# SCH_Shell_MotorsportV2.net
KiCad netlist of a schematic drawn in EasyEDA
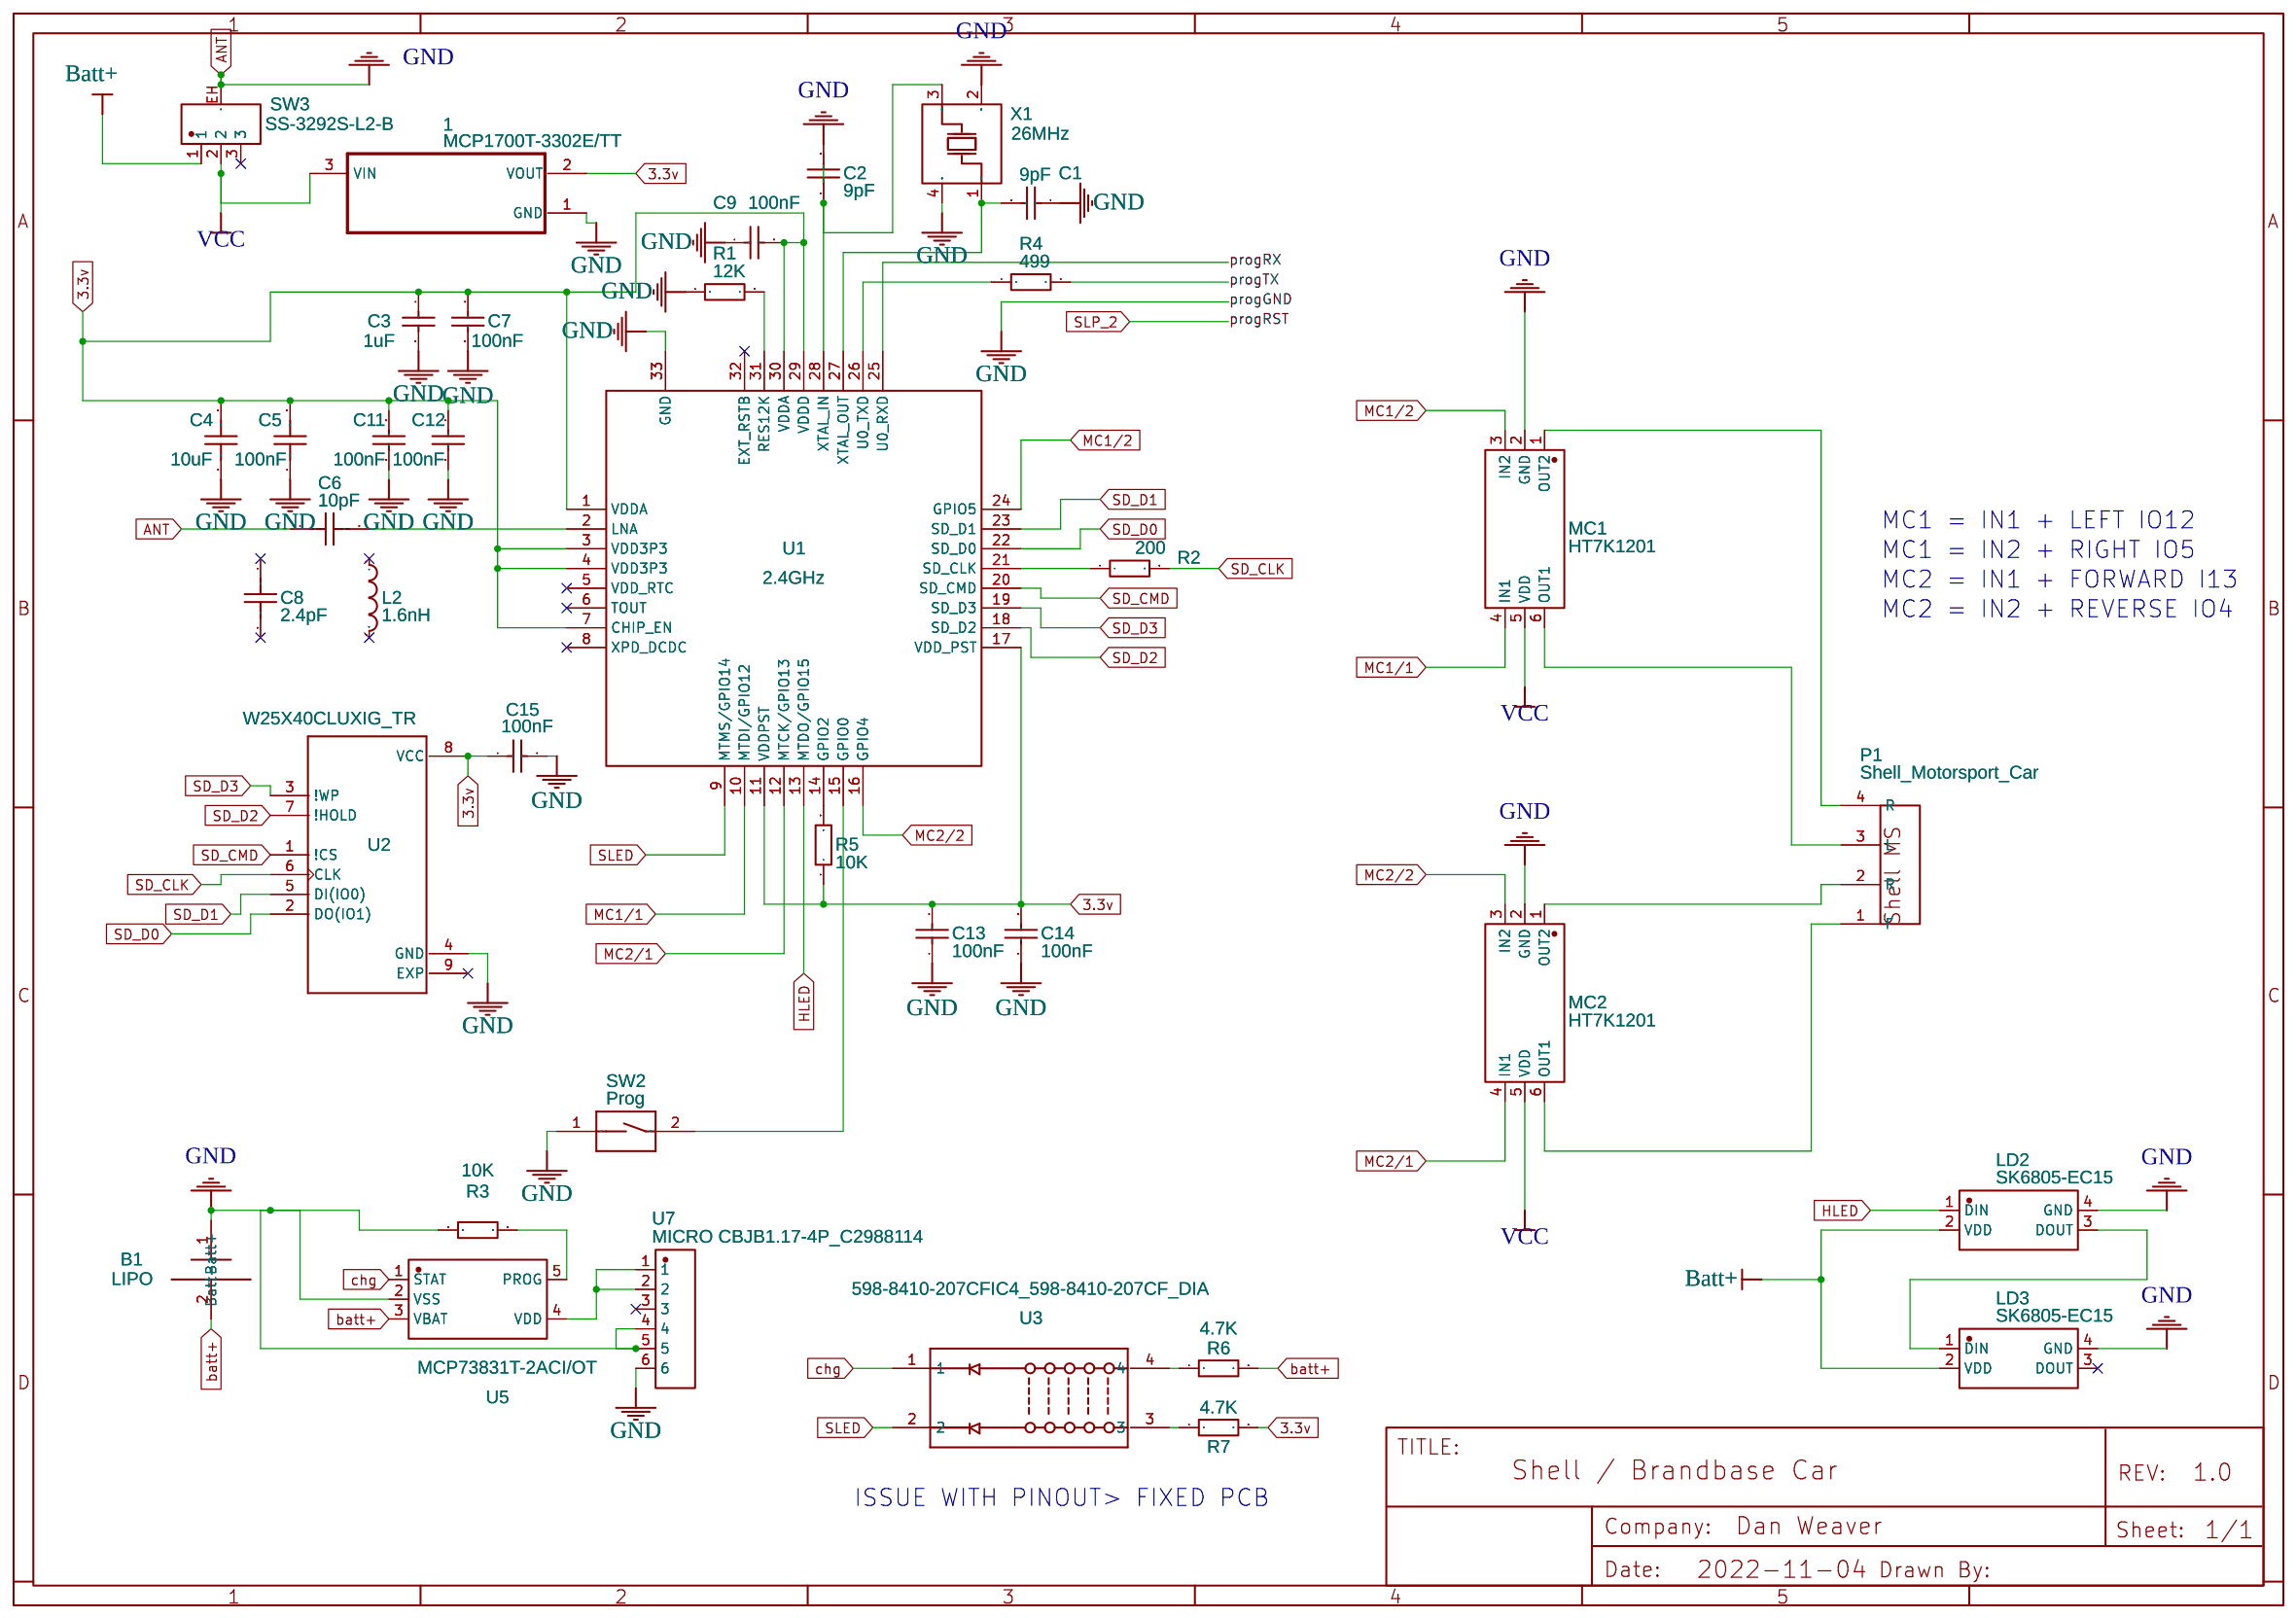
[diagram p0: schematic sheet]

(export (version "E")
  (design (tool "Eeschema 10.0.6"))
  (components
    (comp (ref "1") (value "MCP1700T-3302E/TT") (libsource (lib "") (part "MCP1700T-3302E/TT")))
    (comp (ref "B1") (value "LIPO") (libsource (lib "") (part "LIPO")))
    (comp (ref "C1")
      (value "9pF")
      (fields
        (field (name "BOM_Manufacturer Part") "CL05C090DB5NNNC")
        (field (name "BOM_Supplier Part") "C111805")
      )
      (libsource (lib "") (part "CL05C090DB5NNNC"))
    )
    (comp (ref "C2")
      (value "9pF")
      (fields
        (field (name "BOM_Manufacturer Part") "CL05C090DB5NNNC")
        (field (name "BOM_Supplier Part") "C111805")
      )
      (libsource (lib "") (part "CL05C090DB5NNNC_1"))
    )
    (comp (ref "C3")
      (value "1uF")
      (fields
        (field (name "BOM_Manufacturer Part") "CL10A105KA8NNNC")
        (field (name "BOM_Supplier Part") "C5673")
      )
      (libsource (lib "") (part "CL10A105KA8NNNC"))
    )
    (comp (ref "C4")
      (value "10uF")
      (fields
        (field (name "BOM_Manufacturer Part") "CL10A106MA8NRNC")
        (field (name "BOM_Supplier Part") "C96446")
      )
      (libsource (lib "") (part "CL10A106MA8NRNC"))
    )
    (comp (ref "C5")
      (value "100nF")
      (fields
        (field (name "BOM_Manufacturer Part") "CL10B104KC8NNNC")
        (field (name "BOM_Supplier Part") "C15725")
      )
      (libsource (lib "") (part "CL10B104KC8NNNC"))
    )
    (comp (ref "C6")
      (value "10pF")
      (fields
        (field (name "BOM_Manufacturer Part") "CL05C100JB5NNNC")
        (field (name "BOM_Supplier Part") "C32949")
      )
      (libsource (lib "") (part "CL05C100JB5NNNC"))
    )
    (comp (ref "C7")
      (value "100nF")
      (fields
        (field (name "BOM_Manufacturer Part") "CL05B104KO5NNNC")
        (field (name "BOM_Supplier Part") "C1525")
      )
      (libsource (lib "") (part "CL05B104KO5NNNC_1"))
    )
    (comp (ref "C8")
      (value "2.4pF")
      (fields
        (field (name "BOM_Manufacturer Part") "GJM1555C1H2R4CB01D")
        (field (name "BOM_Supplier Part") "C161317")
      )
      (libsource (lib "") (part "GJM1555C1H2R4CB01D"))
    )
    (comp (ref "C9")
      (value "100nF")
      (fields
        (field (name "BOM_Manufacturer Part") "CL05B104KO5NNNC")
        (field (name "BOM_Supplier Part") "C1525")
      )
      (libsource (lib "") (part "CL05B104KO5NNNC"))
    )
    (comp (ref "C11")
      (value "100nF")
      (fields
        (field (name "BOM_Manufacturer Part") "CL05B104KO5NNNC")
        (field (name "BOM_Supplier Part") "C1525")
      )
      (libsource (lib "") (part "CL05B104KO5NNNC_1"))
    )
    (comp (ref "C12")
      (value "100nF")
      (fields
        (field (name "BOM_Manufacturer Part") "CL05B104KO5NNNC")
        (field (name "BOM_Supplier Part") "C1525")
      )
      (libsource (lib "") (part "CL05B104KO5NNNC_1"))
    )
    (comp (ref "C13")
      (value "100nF")
      (fields
        (field (name "BOM_Manufacturer Part") "CL05B104KO5NNNC")
        (field (name "BOM_Supplier Part") "C1525")
      )
      (libsource (lib "") (part "CL05B104KO5NNNC_1"))
    )
    (comp (ref "C14")
      (value "100nF")
      (fields
        (field (name "BOM_Manufacturer Part") "CL05B104KO5NNNC")
        (field (name "BOM_Supplier Part") "C1525")
      )
      (libsource (lib "") (part "CL05B104KO5NNNC_1"))
    )
    (comp (ref "C15")
      (value "100nF")
      (fields
        (field (name "BOM_Manufacturer Part") "CL05B104KO5NNNC")
        (field (name "BOM_Supplier Part") "C1525")
      )
      (libsource (lib "") (part "CL05B104KO5NNNC"))
    )
    (comp (ref "L2")
      (value "1.6nH")
      (fields
        (field (name "BOM_Manufacturer Part") "MLG1005S1N6BT000")
        (field (name "BOM_Supplier Part") "C87529")
      )
      (libsource (lib "") (part "MLG1005S1N6BT000"))
    )
    (comp (ref "LD2")
      (value "SK6805-EC15")
      (fields (field (name "BOM_Supplier Part") "C2890035"))
      (libsource (lib "") (part "SK6805-EC15"))
    )
    (comp (ref "LD3")
      (value "SK6805-EC15")
      (fields (field (name "BOM_Supplier Part") "C2890035"))
      (libsource (lib "") (part "SK6805-EC15"))
    )
    (comp (ref "MC1")
      (value "HT7K1201")
      (fields (field (name "BOM_Supplier Part") "C182041"))
      (libsource (lib "") (part "HT7K1201"))
    )
    (comp (ref "MC2")
      (value "HT7K1201")
      (fields (field (name "BOM_Supplier Part") "C182041"))
      (libsource (lib "") (part "HT7K1201"))
    )
    (comp (ref "P1") (value "Shell_Motorsport_Car") (libsource (lib "") (part "Shell_Motorsport_Car")))
    (comp (ref "R1")
      (value "12K")
      (fields
        (field (name "BOM_Manufacturer Part") "0402WGF1202TCE")
        (field (name "BOM_Supplier Part") "C25752")
      )
      (libsource (lib "") (part "0402WGF1202TCE"))
    )
    (comp (ref "R2")
      (value "200")
      (fields
        (field (name "BOM_Manufacturer Part") "0402WGF2000TCE")
        (field (name "BOM_Supplier Part") "C25087")
      )
      (libsource (lib "") (part "0402WGF2000TCE"))
    )
    (comp (ref "R3")
      (value "10K")
      (fields
        (field (name "BOM_Manufacturer Part") "0402WGF1202TCE")
        (field (name "BOM_Supplier Part") "C25752")
      )
      (libsource (lib "") (part "0402WGF1202TCE"))
    )
    (comp (ref "R4")
      (value "499")
      (fields
        (field (name "BOM_Manufacturer Part") "0402WGF4990TCE")
        (field (name "BOM_Supplier Part") "C4125")
      )
      (libsource (lib "") (part "0402WGF4990TCE"))
    )
    (comp (ref "R5")
      (value "10K")
      (fields
        (field (name "BOM_Manufacturer Part") "TC0225F1002TCE")
        (field (name "BOM_Supplier Part") "C98838")
      )
      (libsource (lib "") (part "TC0225F1002TCE"))
    )
    (comp (ref "R6")
      (value "4.7K")
      (fields
        (field (name "BOM_Manufacturer Part") "0402WGF1202TCE")
        (field (name "BOM_Supplier Part") "C25752")
      )
      (libsource (lib "") (part "0402WGF1202TCE"))
    )
    (comp (ref "R7")
      (value "4.7K")
      (fields
        (field (name "BOM_Manufacturer Part") "0402WGF1202TCE")
        (field (name "BOM_Supplier Part") "C25752")
      )
      (libsource (lib "") (part "0402WGF1202TCE"))
    )
    (comp (ref "SW2")
      (value "Prog")
      (fields
        (field (name "BOM_Manufacturer Part") "A6TN-1101")
        (field (name "BOM_Supplier Part") "Z12167-ND")
      )
      (libsource (lib "") (part "DIP1"))
    )
    (comp (ref "SW3")
      (value "SS-3292S-L2-B")
      (fields (field (name "BOM_Supplier Part") "C500057"))
      (libsource (lib "") (part "SS-3292S-L2-B"))
    )
    (comp (ref "U1")
      (value "2.4GHz")
      (fields (field (name "BOM_Manufacturer Part") "ESP8266EX") (field (name "BOM_Supplier Part") "C77967"))
      (libsource (lib "") (part "ESP8266EX"))
    )
    (comp (ref "U2") (value "W25X40CLUXIG_TR") (libsource (lib "") (part "W25X40CLUXIG_TR")))
    (comp (ref "U3")
      (value "598-8410-207CFIC4_598-8410-207CF_DIA")
      (libsource (lib "") (part "598-8410-207CFIC4_598-8410-207CF_DIA"))
    )
    (comp (ref "U5")
      (value "MCP73831T-2ACI/OT")
      (fields (field (name "BOM_Supplier Part") "C424093"))
      (libsource (lib "") (part "MCP73831T-2ACI/OT"))
    )
    (comp (ref "U7")
      (value "MICRO CBJB1.17-4P_C2988114")
      (fields
        (field (name "BOM_Manufacturer Part") "MICRO CBJB1.17-4P")
        (field (name "BOM_Supplier Part") "C2988114")
      )
      (libsource (lib "") (part "MICRO CBJB1.17-4P_C2988114"))
    )
    (comp (ref "X1")
      (value "26MHz")
      (fields (field (name "BOM_Supplier Part") "C164056"))
      (libsource (lib "") (part "SMD-3225_4P 26MHz 9pF 10ppm -40&#126;+85℃"))
    )
  )
  (nets
    (net (code "1") (name "/progRX") (class "Default")
      (node (ref "U1") (pin "25") (pinfunction "U0_RXD_25") (pintype "unspecified"))
    )
    (net (code "2") (name "/progTX") (class "Default")
      (node (ref "R4") (pin "2") (pinfunction "2_2") (pintype "input"))
    )
    (net (code "3") (name "3.3v") (class "Default")
      (node (ref "1") (pin "2") (pinfunction "VOUT_2") (pintype "bidirectional"))
      (node (ref "C11") (pin "2") (pinfunction "2_2") (pintype "input"))
      (node (ref "C12") (pin "2") (pinfunction "2_2") (pintype "input"))
      (node (ref "C13") (pin "2") (pinfunction "2_2") (pintype "input"))
      (node (ref "C14") (pin "2") (pinfunction "2_2") (pintype "input"))
      (node (ref "C15") (pin "1") (pinfunction "1_1") (pintype "input"))
      (node (ref "C3") (pin "1") (pinfunction "1_1") (pintype "input"))
      (node (ref "C4") (pin "2") (pinfunction "2_2") (pintype "unspecified"))
      (node (ref "C5") (pin "2") (pinfunction "2_2") (pintype "unspecified"))
      (node (ref "C7") (pin "2") (pinfunction "2_2") (pintype "input"))
      (node (ref "C9") (pin "2") (pinfunction "2_2") (pintype "input"))
      (node (ref "R5") (pin "1") (pinfunction "1_1") (pintype "input"))
      (node (ref "R7") (pin "2") (pinfunction "2_2") (pintype "input"))
      (node (ref "U1") (pin "1") (pinfunction "VDDA_1") (pintype "unspecified"))
      (node (ref "U1") (pin "11") (pinfunction "VDDPST_11") (pintype "unspecified"))
      (node (ref "U1") (pin "17") (pinfunction "VDD_PST_17") (pintype "unspecified"))
      (node (ref "U1") (pin "29") (pinfunction "VDDD_29") (pintype "unspecified"))
      (node (ref "U1") (pin "3") (pinfunction "VDD3P3_3") (pintype "unspecified"))
      (node (ref "U1") (pin "30") (pinfunction "VDDA_30") (pintype "unspecified"))
      (node (ref "U1") (pin "4") (pinfunction "VDD3P3_4") (pintype "unspecified"))
      (node (ref "U1") (pin "7") (pinfunction "CHIP_EN_7") (pintype "unspecified"))
      (node (ref "U2") (pin "8") (pinfunction "VCC_8") (pintype "bidirectional"))
    )
    (net (code "4") (name "ANT") (class "Default")
      (node (ref "1") (pin "1") (pinfunction "GND_1") (pintype "bidirectional"))
      (node (ref "B1") (pin "1") (pinfunction "Batt-_1") (pintype "unspecified"))
      (node (ref "C1") (pin "1") (pinfunction "1_1") (pintype "input"))
      (node (ref "C11") (pin "1") (pinfunction "1_1") (pintype "input"))
      (node (ref "C12") (pin "1") (pinfunction "1_1") (pintype "input"))
      (node (ref "C13") (pin "1") (pinfunction "1_1") (pintype "input"))
      (node (ref "C14") (pin "1") (pinfunction "1_1") (pintype "input"))
      (node (ref "C15") (pin "2") (pinfunction "2_2") (pintype "input"))
      (node (ref "C2") (pin "2") (pinfunction "2_2") (pintype "input"))
      (node (ref "C3") (pin "2") (pinfunction "2_2") (pintype "input"))
      (node (ref "C4") (pin "1") (pinfunction "1_1") (pintype "unspecified"))
      (node (ref "C5") (pin "1") (pinfunction "1_1") (pintype "unspecified"))
      (node (ref "C6") (pin "1") (pinfunction "1_1") (pintype "unspecified"))
      (node (ref "C7") (pin "1") (pinfunction "1_1") (pintype "input"))
      (node (ref "C9") (pin "1") (pinfunction "1_1") (pintype "input"))
      (node (ref "LD2") (pin "4") (pinfunction "GND_4") (pintype "unspecified"))
      (node (ref "LD3") (pin "4") (pinfunction "GND_4") (pintype "unspecified"))
      (node (ref "MC1") (pin "2") (pinfunction "GND_2") (pintype "unspecified"))
      (node (ref "MC2") (pin "2") (pinfunction "GND_2") (pintype "unspecified"))
      (node (ref "R1") (pin "1") (pinfunction "1_1") (pintype "input"))
      (node (ref "R3") (pin "1") (pinfunction "1_1") (pintype "input"))
      (node (ref "SW2") (pin "1") (pinfunction "1_1") (pintype "unspecified"))
      (node (ref "SW3") (pin "EH") (pinfunction "EH_EH") (pintype "unspecified"))
      (node (ref "U1") (pin "33") (pinfunction "GND_33") (pintype "unspecified"))
      (node (ref "U2") (pin "4") (pinfunction "GND_4") (pintype "bidirectional"))
      (node (ref "U5") (pin "2") (pinfunction "VSS_2") (pintype "unspecified"))
      (node (ref "U7") (pin "4") (pinfunction "4_4") (pintype "unspecified"))
      (node (ref "U7") (pin "5") (pinfunction "5_5") (pintype "unspecified"))
      (node (ref "U7") (pin "6") (pinfunction "6_6") (pintype "unspecified"))
      (node (ref "X1") (pin "2") (pinfunction "GND_2") (pintype "unspecified"))
      (node (ref "X1") (pin "4") (pinfunction "GND_4") (pintype "unspecified"))
    )
    (net (code "5") (name "Batt+") (class "Default")
      (node (ref "LD2") (pin "2") (pinfunction "VDD_2") (pintype "unspecified"))
      (node (ref "LD3") (pin "2") (pinfunction "VDD_2") (pintype "unspecified"))
      (node (ref "SW3") (pin "1") (pinfunction "1_1") (pintype "unspecified"))
    )
    (net (code "6") (name "HLED") (class "Default")
      (node (ref "LD2") (pin "1") (pinfunction "DIN_1") (pintype "unspecified"))
      (node (ref "U1") (pin "13") (pinfunction "MTDO/GPIO15_13") (pintype "unspecified"))
    )
    (net (code "7") (name "MC1{slash}1") (class "Default")
      (node (ref "MC1") (pin "4") (pinfunction "IN1_4") (pintype "unspecified"))
      (node (ref "U1") (pin "10") (pinfunction "MTDI/GPIO12_10") (pintype "unspecified"))
    )
    (net (code "8") (name "MC1{slash}2") (class "Default")
      (node (ref "MC1") (pin "3") (pinfunction "IN2_3") (pintype "unspecified"))
      (node (ref "U1") (pin "24") (pinfunction "GPIO5_24") (pintype "unspecified"))
    )
    (net (code "9") (name "MC2{slash}1") (class "Default")
      (node (ref "MC2") (pin "4") (pinfunction "IN1_4") (pintype "unspecified"))
      (node (ref "U1") (pin "12") (pinfunction "MTCK/GPIO13_12") (pintype "unspecified"))
    )
    (net (code "10") (name "MC2{slash}2") (class "Default")
      (node (ref "MC2") (pin "3") (pinfunction "IN2_3") (pintype "unspecified"))
      (node (ref "U1") (pin "16") (pinfunction "GPIO4_16") (pintype "unspecified"))
    )
    (net (code "11") (name "Net-(LD2-DOUT)") (class "Default")
      (node (ref "LD2") (pin "3") (pinfunction "DOUT_3") (pintype "unspecified"))
      (node (ref "LD3") (pin "1") (pinfunction "DIN_1") (pintype "unspecified"))
    )
    (net (code "12") (name "Net-(MC1-OUT1)") (class "Default")
      (node (ref "MC1") (pin "6") (pinfunction "OUT1_6") (pintype "unspecified"))
      (node (ref "P1") (pin "3") (pinfunction "L_3") (pintype "unspecified"))
    )
    (net (code "13") (name "Net-(MC1-OUT2)") (class "Default")
      (node (ref "MC1") (pin "1") (pinfunction "OUT2_1") (pintype "unspecified"))
      (node (ref "P1") (pin "4") (pinfunction "R_4") (pintype "unspecified"))
    )
    (net (code "14") (name "Net-(MC2-OUT1)") (class "Default")
      (node (ref "MC2") (pin "6") (pinfunction "OUT1_6") (pintype "unspecified"))
      (node (ref "P1") (pin "1") (pinfunction "F_1") (pintype "unspecified"))
    )
    (net (code "15") (name "Net-(MC2-OUT2)") (class "Default")
      (node (ref "MC2") (pin "1") (pinfunction "OUT2_1") (pintype "unspecified"))
      (node (ref "P1") (pin "2") (pinfunction "R_2") (pintype "unspecified"))
    )
    (net (code "16") (name "Net-(R6-Pad1)") (class "Default")
      (node (ref "R6") (pin "1") (pinfunction "1_1") (pintype "input"))
      (node (ref "U3") (pin "4") (pinfunction "4_4") (pintype "bidirectional"))
    )
    (net (code "17") (name "Net-(R7-Pad1)") (class "Default")
      (node (ref "R7") (pin "1") (pinfunction "1_1") (pintype "input"))
      (node (ref "U3") (pin "3") (pinfunction "3_3") (pintype "bidirectional"))
    )
    (net (code "18") (name "Net-(U1-GPIO0)") (class "Default")
      (node (ref "SW2") (pin "2") (pinfunction "2_2") (pintype "unspecified"))
      (node (ref "U1") (pin "15") (pinfunction "GPIO0_15") (pintype "unspecified"))
    )
    (net (code "19") (name "Net-(U1-GPIO2)") (class "Default")
      (node (ref "R5") (pin "2") (pinfunction "2_2") (pintype "input"))
      (node (ref "U1") (pin "14") (pinfunction "GPIO2_14") (pintype "unspecified"))
    )
    (net (code "20") (name "Net-(U1-LNA)") (class "Default")
      (node (ref "C6") (pin "2") (pinfunction "2_2") (pintype "unspecified"))
      (node (ref "U1") (pin "2") (pinfunction "LNA_2") (pintype "unspecified"))
    )
    (net (code "21") (name "Net-(U1-RES12K)") (class "Default")
      (node (ref "R1") (pin "2") (pinfunction "2_2") (pintype "input"))
      (node (ref "U1") (pin "31") (pinfunction "RES12K_31") (pintype "unspecified"))
    )
    (net (code "22") (name "Net-(U1-SD_CLK)") (class "Default")
      (node (ref "R2") (pin "1") (pinfunction "1_1") (pintype "input"))
      (node (ref "U1") (pin "21") (pinfunction "SD_CLK_21") (pintype "unspecified"))
    )
    (net (code "23") (name "Net-(U1-U0_TXD)") (class "Default")
      (node (ref "R4") (pin "1") (pinfunction "1_1") (pintype "input"))
      (node (ref "U1") (pin "26") (pinfunction "U0_TXD_26") (pintype "unspecified"))
    )
    (net (code "24") (name "Net-(U1-XTAL_IN)") (class "Default")
      (node (ref "C2") (pin "1") (pinfunction "1_1") (pintype "input"))
      (node (ref "U1") (pin "28") (pinfunction "XTAL_IN_28") (pintype "unspecified"))
      (node (ref "X1") (pin "3") (pinfunction "OSC2_3") (pintype "unspecified"))
    )
    (net (code "25") (name "Net-(U1-XTAL_OUT)") (class "Default")
      (node (ref "C1") (pin "2") (pinfunction "2_2") (pintype "input"))
      (node (ref "U1") (pin "27") (pinfunction "XTAL_OUT_27") (pintype "unspecified"))
      (node (ref "X1") (pin "1") (pinfunction "OSC1_1") (pintype "unspecified"))
    )
    (net (code "26") (name "Net-(U5-PROG)") (class "Default")
      (node (ref "R3") (pin "2") (pinfunction "2_2") (pintype "input"))
      (node (ref "U5") (pin "5") (pinfunction "PROG_5") (pintype "unspecified"))
    )
    (net (code "27") (name "Net-(U5-VDD)") (class "Default")
      (node (ref "U5") (pin "4") (pinfunction "VDD_4") (pintype "unspecified"))
      (node (ref "U7") (pin "1") (pinfunction "1_1") (pintype "unspecified"))
      (node (ref "U7") (pin "2") (pinfunction "2_2") (pintype "unspecified"))
    )
    (net (code "28") (name "SD_CLK") (class "Default")
      (node (ref "R2") (pin "2") (pinfunction "2_2") (pintype "input"))
      (node (ref "U2") (pin "6") (pinfunction "CLK_6") (pintype "bidirectional"))
    )
    (net (code "29") (name "SD_CMD") (class "Default")
      (node (ref "U1") (pin "20") (pinfunction "SD_CMD_20") (pintype "unspecified"))
      (node (ref "U2") (pin "1") (pinfunction "!CS_1") (pintype "bidirectional"))
    )
    (net (code "30") (name "SD_D0") (class "Default")
      (node (ref "U1") (pin "22") (pinfunction "SD_D0_22") (pintype "unspecified"))
      (node (ref "U2") (pin "2") (pinfunction "DO(IO1)_2") (pintype "bidirectional"))
    )
    (net (code "31") (name "SD_D1") (class "Default")
      (node (ref "U1") (pin "23") (pinfunction "SD_D1_23") (pintype "unspecified"))
      (node (ref "U2") (pin "5") (pinfunction "DI(IO0)_5") (pintype "bidirectional"))
    )
    (net (code "32") (name "SD_D2") (class "Default")
      (node (ref "U1") (pin "18") (pinfunction "SD_D2_18") (pintype "unspecified"))
      (node (ref "U2") (pin "7") (pinfunction "!HOLD_7") (pintype "bidirectional"))
    )
    (net (code "33") (name "SD_D3") (class "Default")
      (node (ref "U1") (pin "19") (pinfunction "SD_D3_19") (pintype "unspecified"))
      (node (ref "U2") (pin "3") (pinfunction "!WP_3") (pintype "bidirectional"))
    )
    (net (code "34") (name "SLED") (class "Default")
      (node (ref "U1") (pin "9") (pinfunction "MTMS/GPIO14_9") (pintype "unspecified"))
      (node (ref "U3") (pin "2") (pinfunction "2_2") (pintype "bidirectional"))
    )
    (net (code "36") (name "VCC") (class "Default")
      (node (ref "1") (pin "3") (pinfunction "VIN_3") (pintype "bidirectional"))
      (node (ref "MC1") (pin "5") (pinfunction "VDD_5") (pintype "unspecified"))
      (node (ref "MC2") (pin "5") (pinfunction "VDD_5") (pintype "unspecified"))
      (node (ref "SW3") (pin "2") (pinfunction "2_2") (pintype "unspecified"))
    )
    (net (code "37") (name "batt+") (class "Default")
      (node (ref "B1") (pin "2") (pinfunction "Batt+_2") (pintype "unspecified"))
      (node (ref "R6") (pin "2") (pinfunction "2_2") (pintype "input"))
      (node (ref "U5") (pin "3") (pinfunction "VBAT_3") (pintype "unspecified"))
    )
    (net (code "38") (name "chg") (class "Default")
      (node (ref "U3") (pin "1") (pinfunction "1_1") (pintype "bidirectional"))
      (node (ref "U5") (pin "1") (pinfunction "STAT_1") (pintype "unspecified"))
    )
    (net (code "39") (name "unconnected-(C8-Pad1)") (class "Default")
      (node (ref "C8") (pin "1") (pinfunction "1_1") (pintype "unspecified+no_connect"))
    )
    (net (code "40") (name "unconnected-(C8-Pad2)") (class "Default")
      (node (ref "C8") (pin "2") (pinfunction "2_2") (pintype "unspecified+no_connect"))
    )
    (net (code "41") (name "unconnected-(L2-Pad1)") (class "Default")
      (node (ref "L2") (pin "1") (pinfunction "1_1") (pintype "unspecified+no_connect"))
    )
    (net (code "42") (name "unconnected-(L2-Pad2)") (class "Default")
      (node (ref "L2") (pin "2") (pinfunction "2_2") (pintype "unspecified+no_connect"))
    )
    (net (code "43") (name "unconnected-(LD3-DOUT-Pad3)") (class "Default")
      (node (ref "LD3") (pin "3") (pinfunction "DOUT_3") (pintype "unspecified+no_connect"))
    )
    (net (code "44") (name "unconnected-(SW3-Pad3)") (class "Default")
      (node (ref "SW3") (pin "3") (pinfunction "3_3") (pintype "unspecified+no_connect"))
    )
    (net (code "45") (name "unconnected-(U1-EXT_RSTB-Pad32)") (class "Default")
      (node (ref "U1") (pin "32") (pinfunction "EXT_RSTB_32") (pintype "unspecified+no_connect"))
    )
    (net (code "46") (name "unconnected-(U1-TOUT-Pad6)") (class "Default")
      (node (ref "U1") (pin "6") (pinfunction "TOUT_6") (pintype "unspecified+no_connect"))
    )
    (net (code "47") (name "unconnected-(U1-VDD_RTC-Pad5)") (class "Default")
      (node (ref "U1") (pin "5") (pinfunction "VDD_RTC_5") (pintype "unspecified+no_connect"))
    )
    (net (code "48") (name "unconnected-(U1-XPD_DCDC-Pad8)") (class "Default")
      (node (ref "U1") (pin "8") (pinfunction "XPD_DCDC_8") (pintype "unspecified+no_connect"))
    )
    (net (code "49") (name "unconnected-(U2-EXP-Pad9)") (class "Default")
      (node (ref "U2") (pin "9") (pinfunction "EXP_9") (pintype "bidirectional+no_connect"))
    )
    (net (code "50") (name "unconnected-(U7-Pad3)") (class "Default")
      (node (ref "U7") (pin "3") (pinfunction "3_3") (pintype "unspecified+no_connect"))
    )
  )
)
